# 8_Sensors.net
KiCad netlist of a schematic drawn in Altium Designer
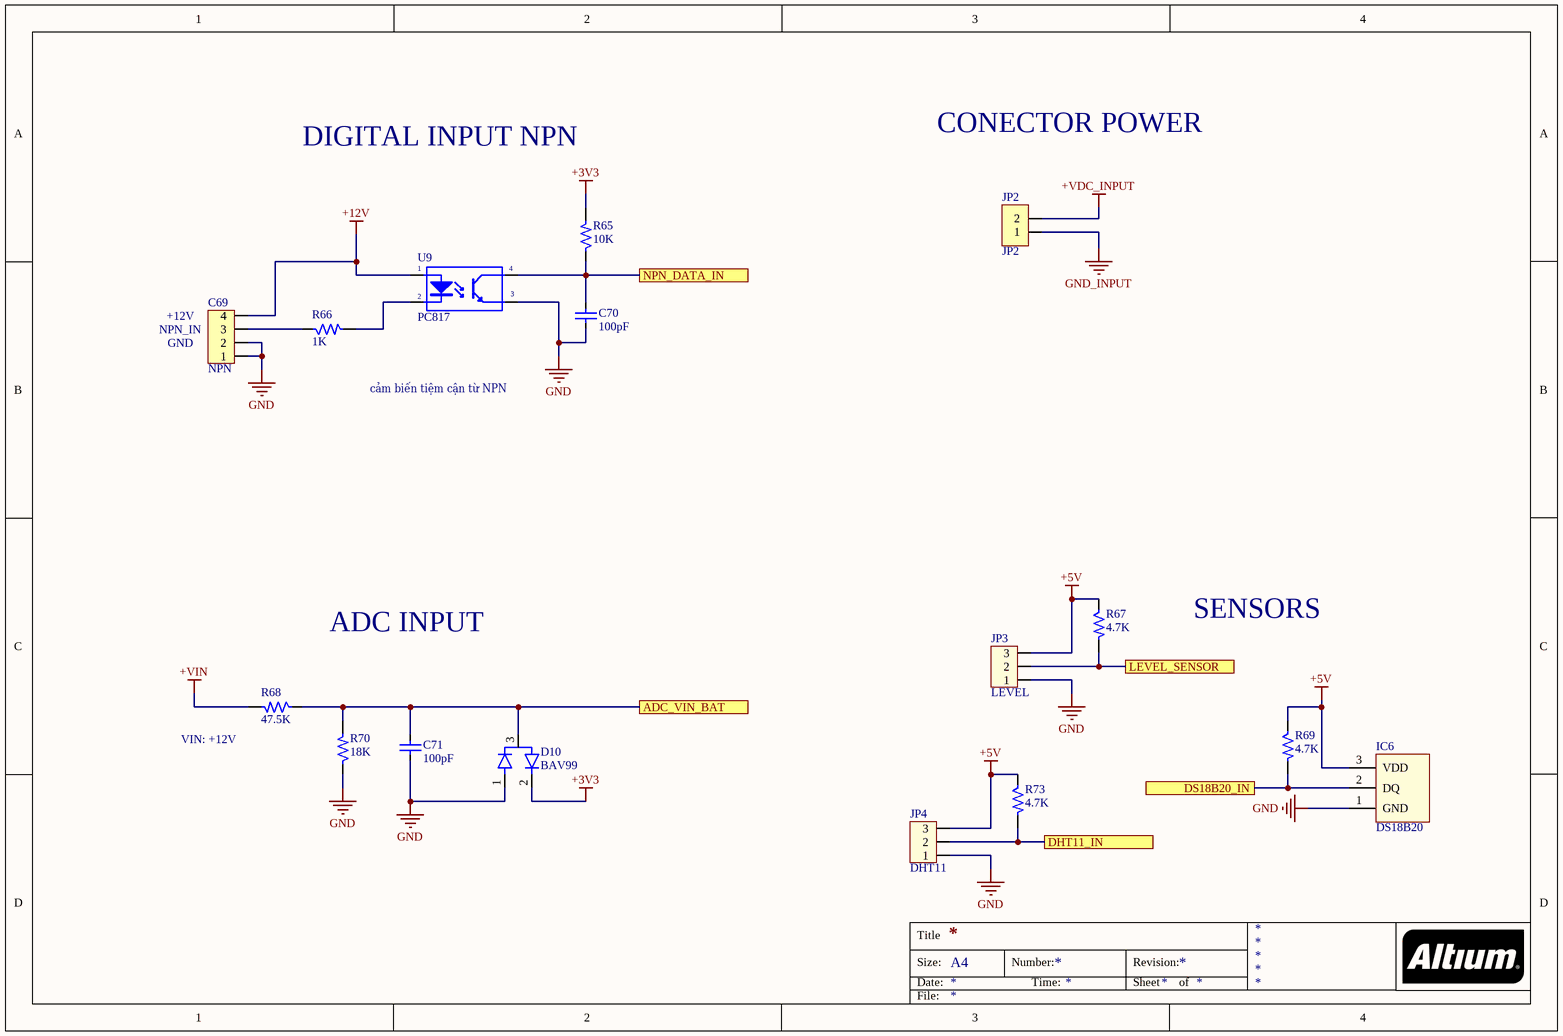
[diagram p0: [8]Sensors.SchDoc]

(export (version "E")
  (design (tool "Eeschema 10.0.6"))
  (components
    (comp (ref "C69")
      (value "NPN")
      (footprint "CON_4P")
      (description "Header IDC, 4 x 1 Pin Vertical 2.54mm Pitch (Non-Boxed, Male)")
      (fields
        (field (name "MANUFACTURER") "Würth Elektronik eiSos GmbH")
        (field (name "PARTNO") "613002143121")
        (field (name "CREATED BY") "Karrer Zheng")
      )
      (libsource (lib "My Library") (part "Header4"))
    )
    (comp (ref "C70")
      (value "100pF")
      (footprint "CAP_0805")
      (description "Capacitor")
      (fields (field (name "PUBLISHER") "Altium Limited"))
      (libsource (lib "My Library") (part "CapSMD"))
    )
    (comp (ref "C71")
      (value "100pF")
      (footprint "CAP_0805")
      (description "Capacitor")
      (fields (field (name "PUBLISHER") "Altium Limited"))
      (libsource (lib "My Library") (part "CapSMD"))
    )
    (comp (ref "D10")
      (value "BAV99")
      (footprint "DIO_BAV99")
      (fields (field (name "MF") "ON Semiconductor"))
      (libsource (lib "BAV99") (part "BAV99"))
    )
    (comp (ref "IC6")
      (value "DS18B20")
      (footprint "DS18S20")
      (description "High Precision  1-Wire® Digital Thermometer")
      (libsource (lib "My Library") (part "DS18S20"))
    )
    (comp (ref "JP2")
      (value "JP2")
      (footprint "JP2-C1T")
      (description "WR-PHD 2.54 mm Angled Socket Header")
      (fields
        (field (name "MANUFACTURER") "Würth Elektronik eiSos GmbH")
        (field (name "PARTNO") "613002143121")
        (field (name "CREATED BY") "Karrer Zheng")
      )
      (libsource (lib "My Library") (part "JP2"))
    )
    (comp (ref "JP3")
      (value "LEVEL")
      (footprint "CON3")
      (description "Connector 3")
      (libsource (lib "My Library") (part "Con3"))
    )
    (comp (ref "JP4")
      (value "DHT11")
      (footprint "CON3")
      (description "Connector 3")
      (libsource (lib "My Library") (part "Con3"))
    )
    (comp (ref "R65")
      (value "10K")
      (footprint "R0805")
      (description "Resistor SMD")
      (libsource (lib "GPS_Traking_V1_1") (part "RM"))
    )
    (comp (ref "R66")
      (value "1K")
      (footprint "R0805")
      (description "Resistor SMD")
      (libsource (lib "GPS_Traking_V1_1") (part "RM"))
    )
    (comp (ref "R67")
      (value "4.7K")
      (footprint "R0805")
      (description "Resistor SMD")
      (libsource (lib "GPS_Traking_V1_1") (part "RM"))
    )
    (comp (ref "R68")
      (value "47.5K")
      (footprint "R0805")
      (description "Resistor SMD")
      (libsource (lib "GPS_Traking_V1_1") (part "RM"))
    )
    (comp (ref "R69")
      (value "4.7K")
      (footprint "R0805")
      (description "Resistor SMD")
      (libsource (lib "GPS_Traking_V1_1") (part "RM"))
    )
    (comp (ref "R70")
      (value "18K")
      (footprint "R0805")
      (description "Resistor SMD")
      (libsource (lib "GPS_Traking_V1_1") (part "RM"))
    )
    (comp (ref "R73")
      (value "4.7K")
      (footprint "R0805")
      (description "Resistor SMD")
      (libsource (lib "GPS_Traking_V1_1") (part "RM"))
    )
    (comp (ref "U9")
      (value "PC817")
      (footprint "SOT254P975X400-4N")
      (description "Single Opto")
      (libsource (lib "My Library") (part "PC817"))
    )
  )
  (nets
    (net (code "1") (name "+3V3") (class "Default")
      (node (ref "D10") (pin "2") (pinfunction "2_2") (pintype "passive"))
      (node (ref "R65") (pin "2") (pinfunction "2_2") (pintype "passive"))
    )
    (net (code "2") (name "+5V") (class "Default")
      (node (ref "IC6") (pin "3") (pinfunction "VDD_3") (pintype "passive"))
      (node (ref "JP3") (pin "3") (pinfunction "3_3") (pintype "passive"))
      (node (ref "JP4") (pin "3") (pinfunction "3_3") (pintype "passive"))
      (node (ref "R67") (pin "1") (pinfunction "1_1") (pintype "passive"))
      (node (ref "R69") (pin "1") (pinfunction "1_1") (pintype "passive"))
      (node (ref "R73") (pin "1") (pinfunction "1_1") (pintype "passive"))
    )
    (net (code "3") (name "+12V") (class "Default")
      (node (ref "C69") (pin "4") (pinfunction "4_4") (pintype "passive"))
      (node (ref "U9") (pin "1") (pinfunction "A_1") (pintype "passive"))
    )
    (net (code "4") (name "+VDC_INPUT") (class "Default")
      (node (ref "JP2") (pin "2") (pinfunction "2_2") (pintype "passive"))
    )
    (net (code "5") (name "+VIN") (class "Default")
      (node (ref "R68") (pin "2") (pinfunction "2_2") (pintype "passive"))
    )
    (net (code "6") (name "/ADC_VIN_BAT") (class "Default")
      (node (ref "C71") (pin "1") (pinfunction "1_1") (pintype "passive"))
      (node (ref "D10") (pin "3") (pinfunction "3_3") (pintype "passive"))
      (node (ref "R68") (pin "1") (pinfunction "1_1") (pintype "passive"))
      (node (ref "R70") (pin "2") (pinfunction "2_2") (pintype "passive"))
    )
    (net (code "7") (name "/DHT11_IN") (class "Default")
      (node (ref "JP4") (pin "2") (pinfunction "2_2") (pintype "passive"))
      (node (ref "R73") (pin "2") (pinfunction "2_2") (pintype "passive"))
    )
    (net (code "8") (name "/DS18B20_IN") (class "Default")
      (node (ref "IC6") (pin "2") (pinfunction "DQ_2") (pintype "passive"))
      (node (ref "R69") (pin "2") (pinfunction "2_2") (pintype "passive"))
    )
    (net (code "9") (name "/LEVEL_SENSOR") (class "Default")
      (node (ref "JP3") (pin "2") (pinfunction "2_2") (pintype "passive"))
      (node (ref "R67") (pin "2") (pinfunction "2_2") (pintype "passive"))
    )
    (net (code "10") (name "/NPN_DATA_IN") (class "Default")
      (node (ref "C70") (pin "1") (pinfunction "1_1") (pintype "passive"))
      (node (ref "R65") (pin "1") (pinfunction "1_1") (pintype "passive"))
      (node (ref "U9") (pin "4") (pinfunction "C_4") (pintype "passive"))
    )
    (net (code "11") (name "GND") (class "Default")
      (node (ref "C69") (pin "1") (pinfunction "1_1") (pintype "passive"))
      (node (ref "C69") (pin "2") (pinfunction "2_2") (pintype "passive"))
      (node (ref "C70") (pin "2") (pinfunction "2_2") (pintype "passive"))
      (node (ref "C71") (pin "2") (pinfunction "2_2") (pintype "passive"))
      (node (ref "D10") (pin "1") (pinfunction "1_1") (pintype "passive"))
      (node (ref "IC6") (pin "1") (pinfunction "GND_1") (pintype "passive"))
      (node (ref "JP3") (pin "1") (pinfunction "1_1") (pintype "passive"))
      (node (ref "JP4") (pin "1") (pinfunction "1_1") (pintype "passive"))
      (node (ref "R70") (pin "1") (pinfunction "1_1") (pintype "passive"))
      (node (ref "U9") (pin "3") (pinfunction "E_3") (pintype "passive"))
    )
    (net (code "12") (name "GND_INPUT") (class "Default")
      (node (ref "JP2") (pin "1") (pinfunction "1_1") (pintype "passive"))
    )
    (net (code "13") (name "Net-(C69-Pad3)") (class "Default")
      (node (ref "C69") (pin "3") (pinfunction "3_3") (pintype "passive"))
      (node (ref "R66") (pin "1") (pinfunction "1_1") (pintype "passive"))
    )
    (net (code "14") (name "Net-(U9-K)") (class "Default")
      (node (ref "R66") (pin "2") (pinfunction "2_2") (pintype "passive"))
      (node (ref "U9") (pin "2") (pinfunction "K_2") (pintype "passive"))
    )
  )
)
